# t10_schem.net
KiCad netlist of a schematic drawn in EAGLE
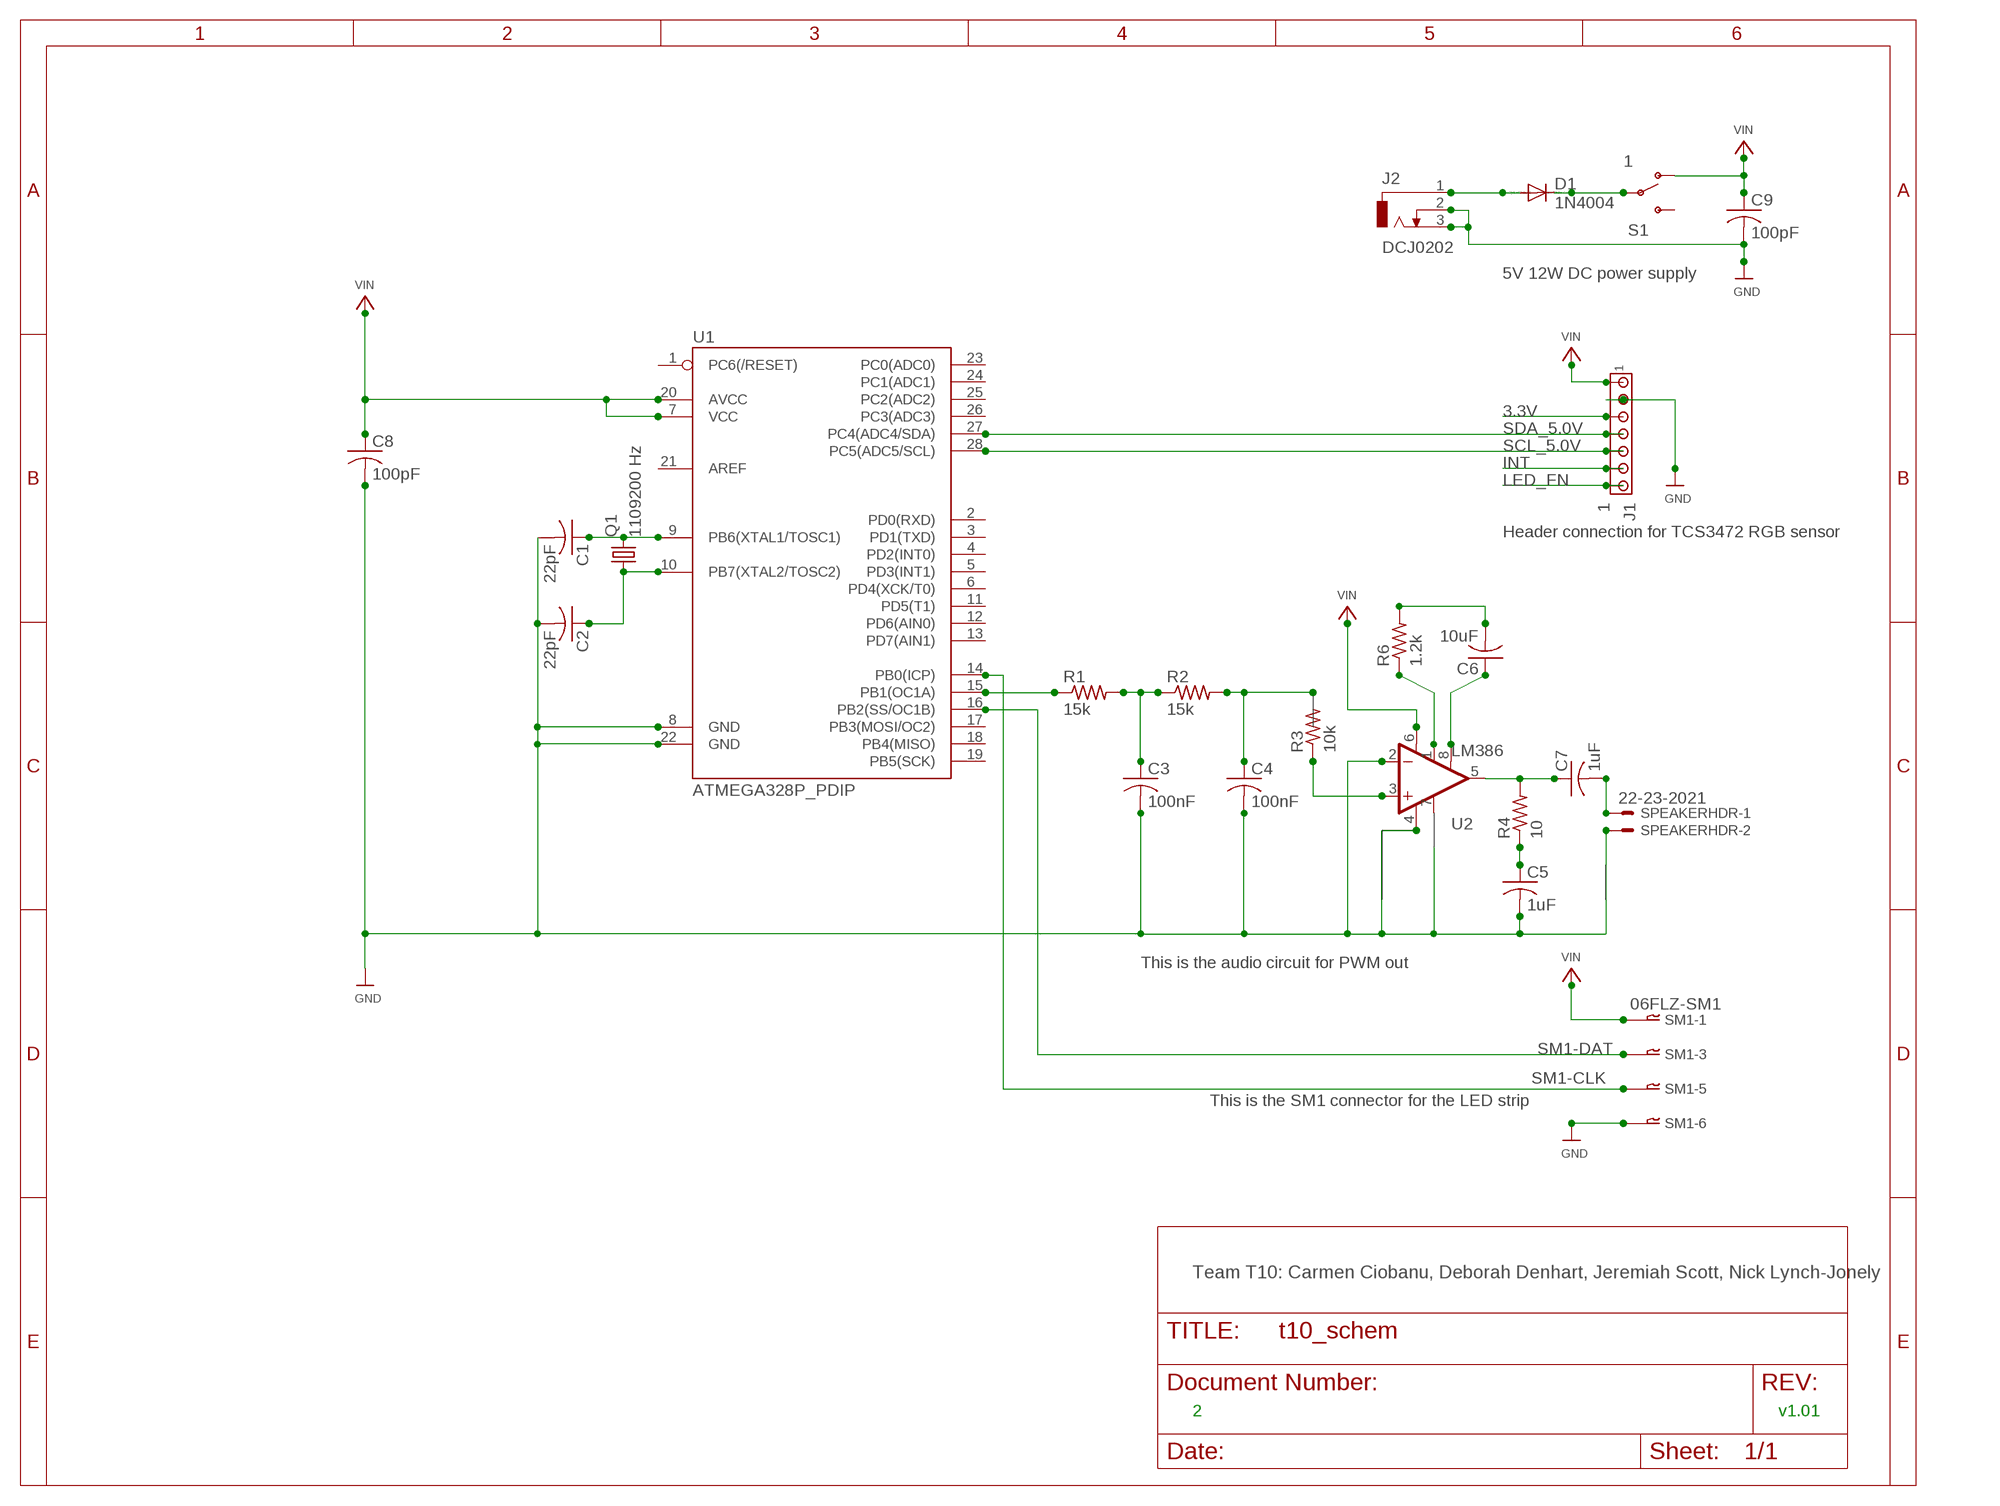
[diagram p0: schematic, sheet 1]

(export (version "E")
  (design (tool "Eeschema 10.0.6"))
  (components
    (comp (ref "C1")
      (value "22pF")
      (footprint "eagle-import:C025-024X044")
      (libsource (lib "eagle-import") (part "C-US025-024X044"))
    )
    (comp (ref "C2")
      (value "22pF")
      (footprint "eagle-import:C025-024X044")
      (libsource (lib "eagle-import") (part "C-US025-024X044"))
    )
    (comp (ref "C3")
      (value "100nF")
      (footprint "eagle-import:C025-024X044")
      (libsource (lib "eagle-import") (part "C-US025-024X044"))
    )
    (comp (ref "C4")
      (value "100nF")
      (footprint "eagle-import:C025-024X044")
      (libsource (lib "eagle-import") (part "C-US025-024X044"))
    )
    (comp (ref "C5")
      (value "1uF")
      (footprint "eagle-import:C025-024X044")
      (libsource (lib "eagle-import") (part "C-US025-024X044"))
    )
    (comp (ref "C6")
      (value "10uF")
      (footprint "eagle-import:C025-024X044")
      (libsource (lib "eagle-import") (part "C-US025-024X044"))
    )
    (comp (ref "C7")
      (value "1uF")
      (footprint "eagle-import:C025-024X044")
      (libsource (lib "eagle-import") (part "C-US025-024X044"))
    )
    (comp (ref "C8")
      (value "100pF")
      (footprint "eagle-import:C025-024X044")
      (libsource (lib "eagle-import") (part "C-US025-024X044"))
    )
    (comp (ref "C9")
      (value "100pF")
      (footprint "eagle-import:C025-024X044")
      (libsource (lib "eagle-import") (part "C-US025-024X044"))
    )
    (comp (ref "D1")
      (value "1N4004")
      (footprint "eagle-import:DO41-10")
      (libsource (lib "eagle-import") (part "1N4004"))
    )
    (comp (ref "J1")
      (value "1")
      (footprint "eagle-import:10X07MTA")
      (libsource (lib "eagle-import") (part "MTA07-100"))
    )
    (comp (ref "J2")
      (value "DCJ0202")
      (footprint "eagle-import:DCJ0202")
      (libsource (lib "eagle-import") (part "DCJ0202"))
    )
    (comp (ref "Q1")
      (value "1109200 Hz")
      (footprint "eagle-import:TC38H")
      (libsource (lib "eagle-import") (part "CRYSTALTC38H"))
    )
    (comp (ref "R1")
      (value "15k")
      (footprint "eagle-import:R0402")
      (libsource (lib "eagle-import") (part "R-US_R0402"))
    )
    (comp (ref "R2")
      (value "15k")
      (footprint "eagle-import:R0402")
      (libsource (lib "eagle-import") (part "R-US_R0402"))
    )
    (comp (ref "R3")
      (value "10k")
      (footprint "eagle-import:M0805")
      (libsource (lib "eagle-import") (part "R-US_M0805"))
    )
    (comp (ref "R4")
      (value "10")
      (footprint "eagle-import:M0805")
      (libsource (lib "eagle-import") (part "R-US_M0805"))
    )
    (comp (ref "R6")
      (value "1.2k")
      (footprint "eagle-import:M0805")
      (libsource (lib "eagle-import") (part "R-US_M0805"))
    )
    (comp (ref "S1")
      (value "1")
      (footprint "eagle-import:SWITCH-SPST-SMD-A")
      (libsource (lib "eagle-import") (part "SWITCH-SPDT-SMD-A"))
    )
    (comp (ref "SM1")
      (value "06FLZ-SM1")
      (footprint "eagle-import:6FLZ-SM")
      (libsource (lib "eagle-import") (part "06FLZ-SM1"))
    )
    (comp (ref "SPEAKERHDR")
      (value "22-23-2021")
      (footprint "eagle-import:22-23-2021")
      (fields (field (name "MF") "MOLEX"))
      (libsource (lib "eagle-import") (part "22-23-2021"))
    )
    (comp (ref "U1")
      (value "ATMEGA328P_PDIP")
      (footprint "eagle-import:DIL28-3")
      (libsource (lib "eagle-import") (part "ATMEGA328P_PDIP"))
    )
    (comp (ref "U2")
      (value "LM386")
      (footprint "eagle-import:DIP08")
      (libsource (lib "eagle-import") (part "LM386"))
    )
  )
  (nets
    (net (code "1") (name "/3.3V") (class "Default")
      (node (ref "J1") (pin "3") (pinfunction "3_3") (pintype "passive"))
    )
    (net (code "2") (name "/INT") (class "Default")
      (node (ref "J1") (pin "6") (pinfunction "6_6") (pintype "passive"))
    )
    (net (code "3") (name "/LED_FN") (class "Default")
      (node (ref "J1") (pin "7") (pinfunction "7_7") (pintype "passive"))
    )
    (net (code "4") (name "/SCL_5.0V") (class "Default")
      (node (ref "J1") (pin "5") (pinfunction "5_5") (pintype "passive"))
      (node (ref "U1") (pin "28") (pinfunction "PC5(ADC5/SCL)_28") (pintype "bidirectional"))
    )
    (net (code "5") (name "/SDA_5.0V") (class "Default")
      (node (ref "J1") (pin "4") (pinfunction "4_4") (pintype "passive"))
      (node (ref "U1") (pin "27") (pinfunction "PC4(ADC4/SDA)_27") (pintype "bidirectional"))
    )
    (net (code "6") (name "/SM1-CLK") (class "Default")
      (node (ref "SM1") (pin "5") (pinfunction "1_5") (pintype "passive"))
      (node (ref "U1") (pin "14") (pinfunction "PB0(ICP)_14") (pintype "bidirectional"))
    )
    (net (code "7") (name "/SM1-DAT") (class "Default")
      (node (ref "SM1") (pin "3") (pinfunction "1_3") (pintype "passive"))
      (node (ref "U1") (pin "16") (pinfunction "PB2(SS/OC1B)_16") (pintype "bidirectional"))
    )
    (net (code "8") (name "GND") (class "Default")
      (node (ref "C1") (pin "2") (pinfunction "2_2") (pintype "passive"))
      (node (ref "C2") (pin "2") (pinfunction "2_2") (pintype "passive"))
      (node (ref "C3") (pin "2") (pinfunction "2_2") (pintype "passive"))
      (node (ref "C4") (pin "2") (pinfunction "2_2") (pintype "passive"))
      (node (ref "C5") (pin "2") (pinfunction "2_2") (pintype "passive"))
      (node (ref "C8") (pin "2") (pinfunction "2_2") (pintype "passive"))
      (node (ref "C9") (pin "2") (pinfunction "2_2") (pintype "passive"))
      (node (ref "J1") (pin "2") (pinfunction "2_2") (pintype "passive"))
      (node (ref "J2") (pin "2") (pinfunction "2_2") (pintype "passive"))
      (node (ref "J2") (pin "3") (pinfunction "3_3") (pintype "passive"))
      (node (ref "SM1") (pin "6") (pinfunction "1_6") (pintype "passive"))
      (node (ref "SPEAKERHDR") (pin "2") (pinfunction "S_2") (pintype "passive"))
      (node (ref "U1") (pin "22") (pinfunction "GND_22") (pintype "bidirectional"))
      (node (ref "U1") (pin "8") (pinfunction "GND_8") (pintype "bidirectional"))
      (node (ref "U2") (pin "2") (pinfunction "-IN_2") (pintype "input"))
      (node (ref "U2") (pin "4") (pinfunction "V-_4") (pintype "power_in"))
      (node (ref "U2") (pin "7") (pinfunction "BP_7") (pintype "bidirectional"))
    )
    (net (code "9") (name "Net-(C3-Pad1)") (class "Default")
      (node (ref "C3") (pin "1") (pinfunction "1_1") (pintype "passive"))
      (node (ref "R1") (pin "2") (pinfunction "2_2") (pintype "passive"))
      (node (ref "R2") (pin "1") (pinfunction "1_1") (pintype "passive"))
    )
    (net (code "10") (name "Net-(C4-Pad1)") (class "Default")
      (node (ref "C4") (pin "1") (pinfunction "1_1") (pintype "passive"))
      (node (ref "R2") (pin "2") (pinfunction "2_2") (pintype "passive"))
      (node (ref "R3") (pin "2") (pinfunction "2_2") (pintype "passive"))
    )
    (net (code "11") (name "Net-(C5-Pad1)") (class "Default")
      (node (ref "C5") (pin "1") (pinfunction "1_1") (pintype "passive"))
      (node (ref "R4") (pin "1") (pinfunction "1_1") (pintype "passive"))
    )
    (net (code "12") (name "Net-(C6-Pad1)") (class "Default")
      (node (ref "C6") (pin "1") (pinfunction "1_1") (pintype "passive"))
      (node (ref "U2") (pin "8") (pinfunction "GAIN_8") (pintype "bidirectional"))
    )
    (net (code "13") (name "Net-(C6-Pad2)") (class "Default")
      (node (ref "C6") (pin "2") (pinfunction "2_2") (pintype "passive"))
      (node (ref "R6") (pin "2") (pinfunction "2_2") (pintype "passive"))
    )
    (net (code "14") (name "Net-(D1-PadA)") (class "Default")
      (node (ref "D1") (pin "A") (pinfunction "A_A") (pintype "passive"))
      (node (ref "J2") (pin "1") (pinfunction "1_1") (pintype "passive"))
    )
    (net (code "15") (name "Net-(R6-Pad1)") (class "Default")
      (node (ref "R6") (pin "1") (pinfunction "1_1") (pintype "passive"))
      (node (ref "U2") (pin "1") (pinfunction "GAIN_1") (pintype "bidirectional"))
    )
    (net (code "16") (name "Net-(S1-P)") (class "Default")
      (node (ref "D1") (pin "C") (pinfunction "C_C") (pintype "passive"))
      (node (ref "S1") (pin "2") (pinfunction "P_2") (pintype "passive"))
    )
    (net (code "17") (name "Net-(SPEAKERHDRA-S)") (class "Default")
      (node (ref "C7") (pin "2") (pinfunction "2_2") (pintype "passive"))
      (node (ref "SPEAKERHDR") (pin "1") (pinfunction "S_1") (pintype "passive"))
    )
    (net (code "18") (name "Net-(U1-PB1(OC1A))") (class "Default")
      (node (ref "R1") (pin "1") (pinfunction "1_1") (pintype "passive"))
      (node (ref "U1") (pin "15") (pinfunction "PB1(OC1A)_15") (pintype "bidirectional"))
    )
    (net (code "19") (name "Net-(U1-PB6(XTAL1{slash}TOSC1))") (class "Default")
      (node (ref "C1") (pin "1") (pinfunction "1_1") (pintype "passive"))
      (node (ref "Q1") (pin "2") (pinfunction "2_2") (pintype "passive"))
      (node (ref "U1") (pin "9") (pinfunction "PB6(XTAL1/TOSC1)_9") (pintype "bidirectional"))
    )
    (net (code "20") (name "Net-(U1-PB7(XTAL2{slash}TOSC2))") (class "Default")
      (node (ref "C2") (pin "1") (pinfunction "1_1") (pintype "passive"))
      (node (ref "Q1") (pin "1") (pinfunction "1_1") (pintype "passive"))
      (node (ref "U1") (pin "10") (pinfunction "PB7(XTAL2/TOSC2)_10") (pintype "bidirectional"))
    )
    (net (code "21") (name "Net-(U2-+IN)") (class "Default")
      (node (ref "R3") (pin "1") (pinfunction "1_1") (pintype "passive"))
      (node (ref "U2") (pin "3") (pinfunction "+IN_3") (pintype "input"))
    )
    (net (code "22") (name "Net-(U2-OUT)") (class "Default")
      (node (ref "C7") (pin "1") (pinfunction "1_1") (pintype "passive"))
      (node (ref "R4") (pin "2") (pinfunction "2_2") (pintype "passive"))
      (node (ref "U2") (pin "5") (pinfunction "OUT_5") (pintype "output"))
    )
    (net (code "23") (name "VIN") (class "Default")
      (node (ref "C8") (pin "1") (pinfunction "1_1") (pintype "passive"))
      (node (ref "C9") (pin "1") (pinfunction "1_1") (pintype "passive"))
      (node (ref "J1") (pin "1") (pinfunction "1_1") (pintype "passive"))
      (node (ref "S1") (pin "1") (pinfunction "O_1") (pintype "passive"))
      (node (ref "SM1") (pin "1") (pinfunction "1_1") (pintype "passive"))
      (node (ref "U1") (pin "20") (pinfunction "AVCC_20") (pintype "bidirectional"))
      (node (ref "U1") (pin "7") (pinfunction "VCC_7") (pintype "bidirectional"))
      (node (ref "U2") (pin "6") (pinfunction "V+_6") (pintype "power_in"))
    )
    (net (code "24") (name "unconnected-(S1-S-Pad3)") (class "Default")
      (node (ref "S1") (pin "3") (pinfunction "S_3") (pintype "passive"))
    )
    (net (code "25") (name "unconnected-(U1-AREF-Pad21)") (class "Default")
      (node (ref "U1") (pin "21") (pinfunction "AREF_21") (pintype "bidirectional"))
    )
    (net (code "26") (name "unconnected-(U1-PB3(MOSI{slash}OC2)-Pad17)") (class "Default")
      (node (ref "U1") (pin "17") (pinfunction "PB3(MOSI/OC2)_17") (pintype "bidirectional"))
    )
    (net (code "27") (name "unconnected-(U1-PB4(MISO)-Pad18)") (class "Default")
      (node (ref "U1") (pin "18") (pinfunction "PB4(MISO)_18") (pintype "bidirectional"))
    )
    (net (code "28") (name "unconnected-(U1-PB5(SCK)-Pad19)") (class "Default")
      (node (ref "U1") (pin "19") (pinfunction "PB5(SCK)_19") (pintype "bidirectional"))
    )
    (net (code "29") (name "unconnected-(U1-PC0(ADC0)-Pad23)") (class "Default")
      (node (ref "U1") (pin "23") (pinfunction "PC0(ADC0)_23") (pintype "bidirectional"))
    )
    (net (code "30") (name "unconnected-(U1-PC1(ADC1)-Pad24)") (class "Default")
      (node (ref "U1") (pin "24") (pinfunction "PC1(ADC1)_24") (pintype "bidirectional"))
    )
    (net (code "31") (name "unconnected-(U1-PC2(ADC2)-Pad25)") (class "Default")
      (node (ref "U1") (pin "25") (pinfunction "PC2(ADC2)_25") (pintype "bidirectional"))
    )
    (net (code "32") (name "unconnected-(U1-PC3(ADC3)-Pad26)") (class "Default")
      (node (ref "U1") (pin "26") (pinfunction "PC3(ADC3)_26") (pintype "bidirectional"))
    )
    (net (code "33") (name "unconnected-(U1-PC6({slash}RESET)-Pad1)") (class "Default")
      (node (ref "U1") (pin "1") (pinfunction "PC6(/RESET)_1") (pintype "bidirectional"))
    )
    (net (code "34") (name "unconnected-(U1-PD0(RXD)-Pad2)") (class "Default")
      (node (ref "U1") (pin "2") (pinfunction "PD0(RXD)_2") (pintype "bidirectional"))
    )
    (net (code "35") (name "unconnected-(U1-PD1(TXD)-Pad3)") (class "Default")
      (node (ref "U1") (pin "3") (pinfunction "PD1(TXD)_3") (pintype "bidirectional"))
    )
    (net (code "36") (name "unconnected-(U1-PD2(INT0)-Pad4)") (class "Default")
      (node (ref "U1") (pin "4") (pinfunction "PD2(INT0)_4") (pintype "bidirectional"))
    )
    (net (code "37") (name "unconnected-(U1-PD3(INT1)-Pad5)") (class "Default")
      (node (ref "U1") (pin "5") (pinfunction "PD3(INT1)_5") (pintype "bidirectional"))
    )
    (net (code "38") (name "unconnected-(U1-PD4(XCK{slash}T0)-Pad6)") (class "Default")
      (node (ref "U1") (pin "6") (pinfunction "PD4(XCK/T0)_6") (pintype "bidirectional"))
    )
    (net (code "39") (name "unconnected-(U1-PD5(T1)-Pad11)") (class "Default")
      (node (ref "U1") (pin "11") (pinfunction "PD5(T1)_11") (pintype "bidirectional"))
    )
    (net (code "40") (name "unconnected-(U1-PD6(AIN0)-Pad12)") (class "Default")
      (node (ref "U1") (pin "12") (pinfunction "PD6(AIN0)_12") (pintype "bidirectional"))
    )
    (net (code "41") (name "unconnected-(U1-PD7(AIN1)-Pad13)") (class "Default")
      (node (ref "U1") (pin "13") (pinfunction "PD7(AIN1)_13") (pintype "bidirectional"))
    )
  )
)
